# one_digit.net
KiCad netlist of a schematic drawn in EAGLE
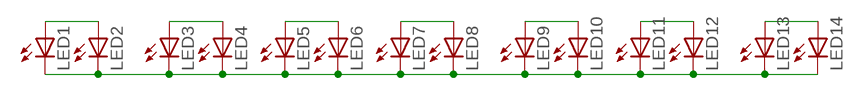
[diagram p0: schematic, sheet 1]

(export (version "E")
  (design (tool "Eeschema 10.0.6"))
  (components
    (comp (ref "LED1")
      (value "LED5MM")
      (footprint "eagle-import:LED5MM")
      (libsource (lib "eagle-import") (part "LED5MM"))
    )
    (comp (ref "LED2")
      (value "LED5MM")
      (footprint "eagle-import:LED5MM")
      (libsource (lib "eagle-import") (part "LED5MM"))
    )
    (comp (ref "LED3")
      (value "LED5MM")
      (footprint "eagle-import:LED5MM")
      (libsource (lib "eagle-import") (part "LED5MM"))
    )
    (comp (ref "LED4")
      (value "LED5MM")
      (footprint "eagle-import:LED5MM")
      (libsource (lib "eagle-import") (part "LED5MM"))
    )
    (comp (ref "LED5")
      (value "LED5MM")
      (footprint "eagle-import:LED5MM")
      (libsource (lib "eagle-import") (part "LED5MM"))
    )
    (comp (ref "LED6")
      (value "LED5MM")
      (footprint "eagle-import:LED5MM")
      (libsource (lib "eagle-import") (part "LED5MM"))
    )
    (comp (ref "LED7")
      (value "LED5MM")
      (footprint "eagle-import:LED5MM")
      (libsource (lib "eagle-import") (part "LED5MM"))
    )
    (comp (ref "LED8")
      (value "LED5MM")
      (footprint "eagle-import:LED5MM")
      (libsource (lib "eagle-import") (part "LED5MM"))
    )
    (comp (ref "LED9")
      (value "LED5MM")
      (footprint "eagle-import:LED5MM")
      (libsource (lib "eagle-import") (part "LED5MM"))
    )
    (comp (ref "LED10")
      (value "LED5MM")
      (footprint "eagle-import:LED5MM")
      (libsource (lib "eagle-import") (part "LED5MM"))
    )
    (comp (ref "LED11")
      (value "LED5MM")
      (footprint "eagle-import:LED5MM")
      (libsource (lib "eagle-import") (part "LED5MM"))
    )
    (comp (ref "LED12")
      (value "LED5MM")
      (footprint "eagle-import:LED5MM")
      (libsource (lib "eagle-import") (part "LED5MM"))
    )
    (comp (ref "LED13")
      (value "LED5MM")
      (footprint "eagle-import:LED5MM")
      (libsource (lib "eagle-import") (part "LED5MM"))
    )
    (comp (ref "LED14")
      (value "LED5MM")
      (footprint "eagle-import:LED5MM")
      (libsource (lib "eagle-import") (part "LED5MM"))
    )
  )
  (nets
    (net (code "1") (name "Net-(LED1-C)") (class "Default")
      (node (ref "LED1") (pin "K") (pinfunction "C_K") (pintype "passive"))
      (node (ref "LED10") (pin "K") (pinfunction "C_K") (pintype "passive"))
      (node (ref "LED11") (pin "K") (pinfunction "C_K") (pintype "passive"))
      (node (ref "LED12") (pin "K") (pinfunction "C_K") (pintype "passive"))
      (node (ref "LED13") (pin "K") (pinfunction "C_K") (pintype "passive"))
      (node (ref "LED14") (pin "K") (pinfunction "C_K") (pintype "passive"))
      (node (ref "LED2") (pin "K") (pinfunction "C_K") (pintype "passive"))
      (node (ref "LED3") (pin "K") (pinfunction "C_K") (pintype "passive"))
      (node (ref "LED4") (pin "K") (pinfunction "C_K") (pintype "passive"))
      (node (ref "LED5") (pin "K") (pinfunction "C_K") (pintype "passive"))
      (node (ref "LED6") (pin "K") (pinfunction "C_K") (pintype "passive"))
      (node (ref "LED7") (pin "K") (pinfunction "C_K") (pintype "passive"))
      (node (ref "LED8") (pin "K") (pinfunction "C_K") (pintype "passive"))
      (node (ref "LED9") (pin "K") (pinfunction "C_K") (pintype "passive"))
    )
    (net (code "2") (name "Net-(LED1-PadA)") (class "Default")
      (node (ref "LED1") (pin "A") (pinfunction "A_A") (pintype "passive"))
      (node (ref "LED2") (pin "A") (pinfunction "A_A") (pintype "passive"))
    )
    (net (code "3") (name "Net-(LED3-PadA)") (class "Default")
      (node (ref "LED3") (pin "A") (pinfunction "A_A") (pintype "passive"))
      (node (ref "LED4") (pin "A") (pinfunction "A_A") (pintype "passive"))
    )
    (net (code "4") (name "Net-(LED5-PadA)") (class "Default")
      (node (ref "LED5") (pin "A") (pinfunction "A_A") (pintype "passive"))
      (node (ref "LED6") (pin "A") (pinfunction "A_A") (pintype "passive"))
    )
    (net (code "5") (name "Net-(LED7-PadA)") (class "Default")
      (node (ref "LED7") (pin "A") (pinfunction "A_A") (pintype "passive"))
      (node (ref "LED8") (pin "A") (pinfunction "A_A") (pintype "passive"))
    )
    (net (code "6") (name "Net-(LED10-PadA)") (class "Default")
      (node (ref "LED10") (pin "A") (pinfunction "A_A") (pintype "passive"))
      (node (ref "LED9") (pin "A") (pinfunction "A_A") (pintype "passive"))
    )
    (net (code "7") (name "Net-(LED11-PadA)") (class "Default")
      (node (ref "LED11") (pin "A") (pinfunction "A_A") (pintype "passive"))
      (node (ref "LED12") (pin "A") (pinfunction "A_A") (pintype "passive"))
    )
    (net (code "8") (name "Net-(LED13-PadA)") (class "Default")
      (node (ref "LED13") (pin "A") (pinfunction "A_A") (pintype "passive"))
      (node (ref "LED14") (pin "A") (pinfunction "A_A") (pintype "passive"))
    )
  )
)
